# single_sensor.net
KiCad netlist of a schematic drawn in EAGLE
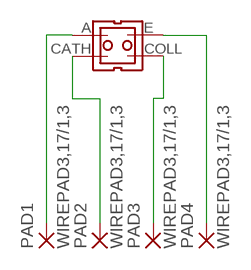
[diagram p0: schematic, sheet 1]

(export (version "E")
  (design (tool "Eeschema 10.0.6"))
  (components
    (comp (ref "PAD1")
      (value "WIREPAD3,17/1,3")
      (footprint "eagle-import:3,17_1,3")
      (libsource (lib "eagle-import") (part "WIREPAD3,17/1,3"))
    )
    (comp (ref "PAD2")
      (value "WIREPAD3,17/1,3")
      (footprint "eagle-import:3,17_1,3")
      (libsource (lib "eagle-import") (part "WIREPAD3,17/1,3"))
    )
    (comp (ref "PAD3")
      (value "WIREPAD3,17/1,3")
      (footprint "eagle-import:3,17_1,3")
      (libsource (lib "eagle-import") (part "WIREPAD3,17/1,3"))
    )
    (comp (ref "PAD4")
      (value "WIREPAD3,17/1,3")
      (footprint "eagle-import:3,17_1,3")
      (libsource (lib "eagle-import") (part "WIREPAD3,17/1,3"))
    )
    (comp (ref "U$1")
      (value "CNY70")
      (footprint "eagle-import:CNY70")
      (libsource (lib "eagle-import") (part "CNY70"))
    )
  )
  (nets
    (net (code "1") (name "Net-(PAD1-P)") (class "Default")
      (node (ref "PAD1") (pin "1") (pinfunction "P_1") (pintype "passive"))
      (node (ref "U$1") (pin "A") (pinfunction "5V(DIG)_A") (pintype "power_in"))
    )
    (net (code "2") (name "Net-(PAD2-P)") (class "Default")
      (node (ref "PAD2") (pin "1") (pinfunction "P_1") (pintype "passive"))
      (node (ref "U$1") (pin "CATH") (pinfunction "GND(DIG)_CATH") (pintype "power_in"))
    )
    (net (code "3") (name "Net-(PAD3-P)") (class "Default")
      (node (ref "PAD3") (pin "1") (pinfunction "P_1") (pintype "passive"))
      (node (ref "U$1") (pin "COLL") (pinfunction "5V(PWR)_COLL") (pintype "power_in"))
    )
    (net (code "4") (name "Net-(PAD4-P)") (class "Default")
      (node (ref "PAD4") (pin "1") (pinfunction "P_1") (pintype "passive"))
      (node (ref "U$1") (pin "E") (pinfunction "GND(PWR)_E") (pintype "power_in"))
    )
  )
)
